# M617E.net
KiCad netlist of a schematic drawn in EAGLE
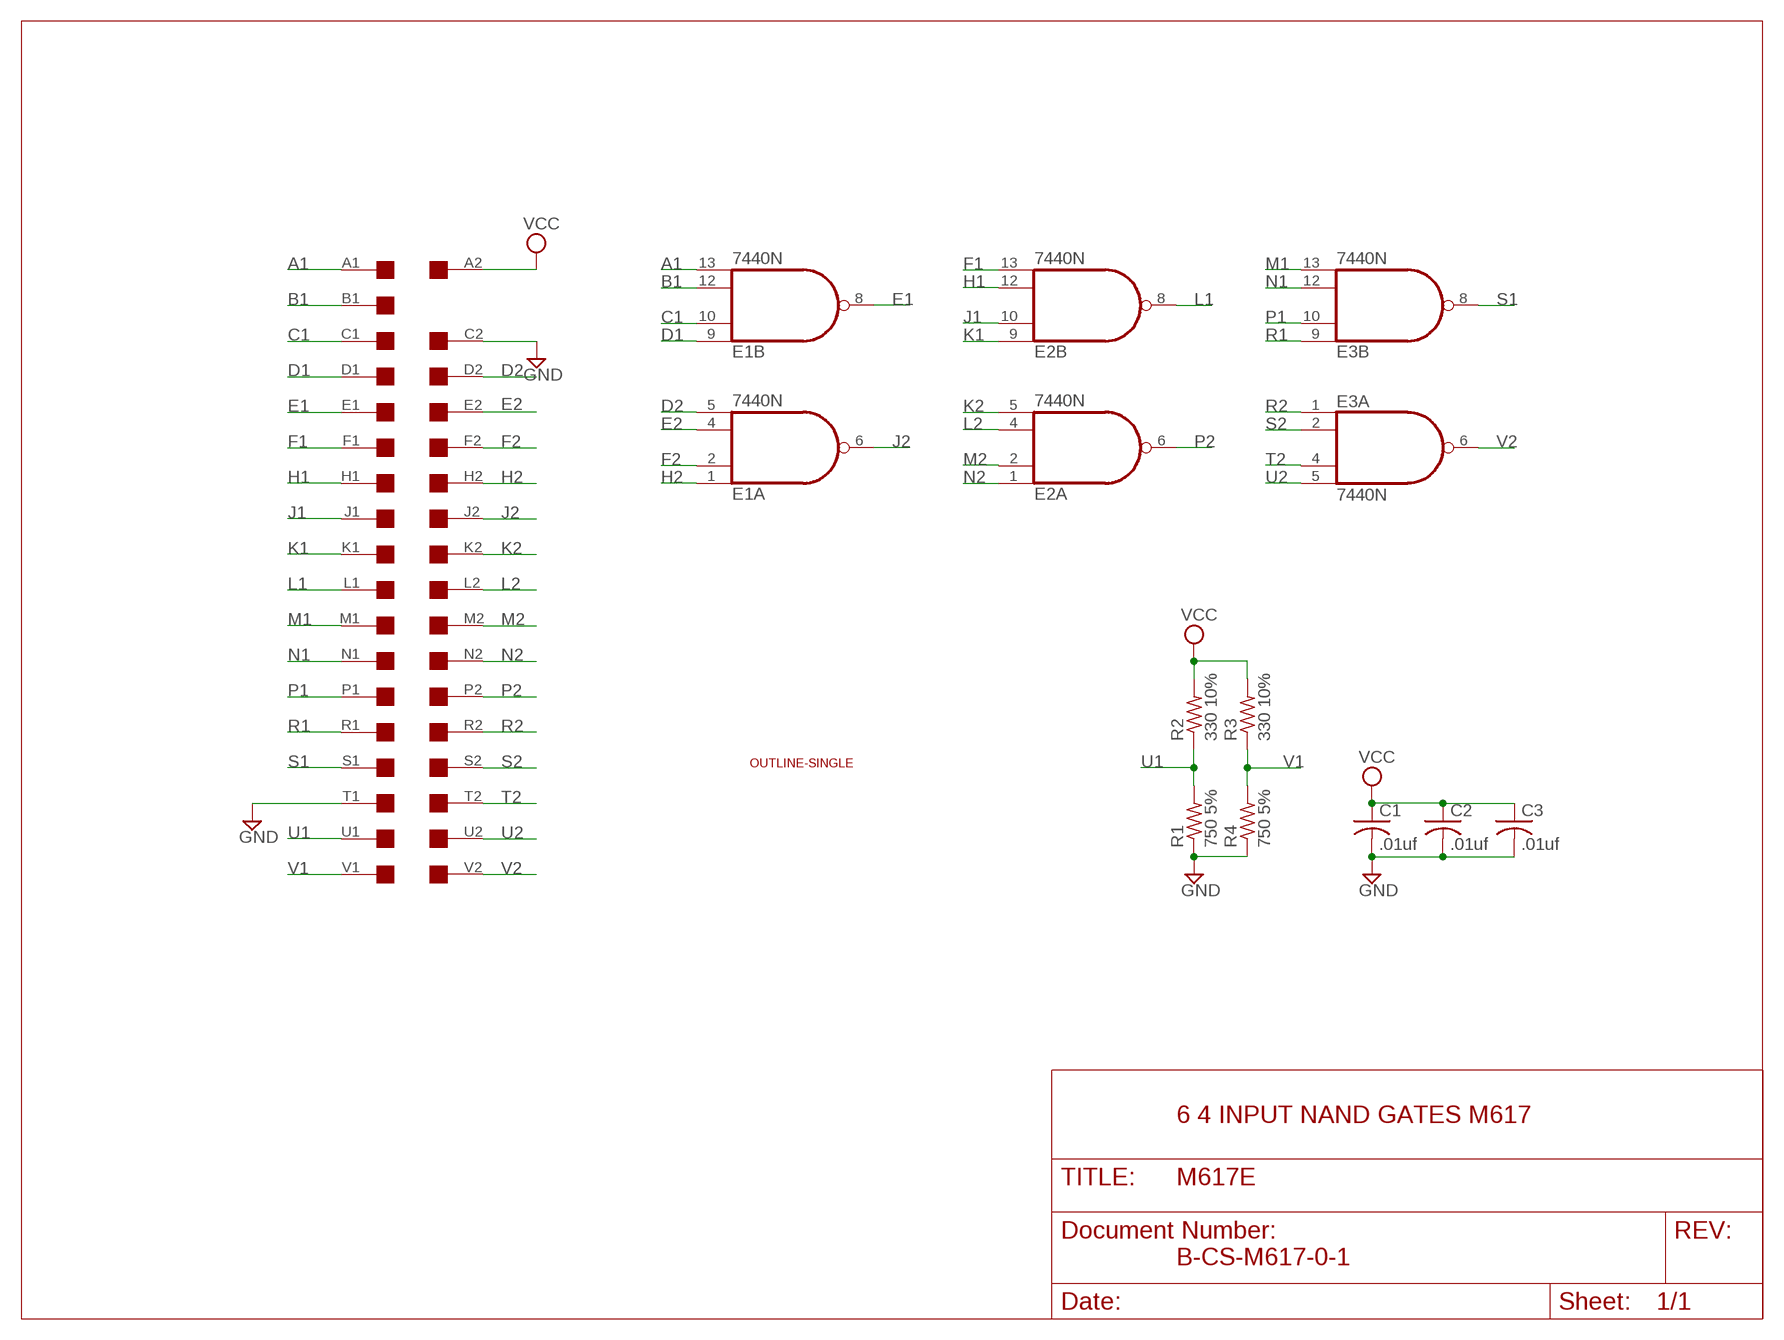
[diagram p0: schematic, sheet 1]

(export (version "E")
  (design (tool "Eeschema 10.0.6"))
  (components
    (comp (ref "C1")
      (value ".01uf")
      (footprint "eagle-import:C050-025X075")
      (libsource (lib "eagle-import") (part "C-US050-025X075"))
    )
    (comp (ref "C2")
      (value ".01uf")
      (footprint "eagle-import:C050-025X075")
      (libsource (lib "eagle-import") (part "C-US050-025X075"))
    )
    (comp (ref "C3")
      (value ".01uf")
      (footprint "eagle-import:C050-025X075")
      (libsource (lib "eagle-import") (part "C-US050-025X075"))
    )
    (comp (ref "E1")
      (value "7440N")
      (footprint "eagle-import:DIL14")
      (libsource (lib "eagle-import") (part "7420NS"))
    )
    (comp (ref "E2")
      (value "7440N")
      (footprint "eagle-import:DIL14")
      (libsource (lib "eagle-import") (part "7420NS"))
    )
    (comp (ref "E3")
      (value "7440N")
      (footprint "eagle-import:DIL14")
      (libsource (lib "eagle-import") (part "7420NS"))
    )
    (comp (ref "R1")
      (value "750 5%")
      (footprint "eagle-import:0207_10")
      (libsource (lib "eagle-import") (part "R-US_0207/10"))
    )
    (comp (ref "R2")
      (value "330 10%")
      (footprint "eagle-import:0207_10")
      (libsource (lib "eagle-import") (part "R-US_0207/10"))
    )
    (comp (ref "R3")
      (value "330 10%")
      (footprint "eagle-import:0207_10")
      (libsource (lib "eagle-import") (part "R-US_0207/10"))
    )
    (comp (ref "R4")
      (value "750 5%")
      (footprint "eagle-import:0207_10")
      (libsource (lib "eagle-import") (part "R-US_0207/10"))
    )
    (comp (ref "U$1")
      (value "SINGLE")
      (footprint "eagle-import:EDGE-CON2")
      (libsource (lib "eagle-import") (part "SINGLE"))
    )
    (comp (ref "U$4")
      (value "OUTLINE-SINGLE")
      (footprint "eagle-import:SINGLE")
      (libsource (lib "eagle-import") (part "OUTLINE-SINGLE"))
    )
  )
  (nets
    (net (code "1") (name "/A1") (class "Default")
      (node (ref "E1") (pin "13") (pinfunction "I3_13") (pintype "input"))
      (node (ref "U$1") (pin "A1") (pinfunction "1_A1") (pintype "bidirectional"))
    )
    (net (code "2") (name "/B1") (class "Default")
      (node (ref "E1") (pin "12") (pinfunction "I2_12") (pintype "input"))
      (node (ref "U$1") (pin "B1") (pinfunction "1_B1") (pintype "bidirectional"))
    )
    (net (code "3") (name "/C1") (class "Default")
      (node (ref "E1") (pin "10") (pinfunction "I1_10") (pintype "input"))
      (node (ref "U$1") (pin "C1") (pinfunction "1_C1") (pintype "bidirectional"))
    )
    (net (code "4") (name "/D1") (class "Default")
      (node (ref "E1") (pin "9") (pinfunction "I0_9") (pintype "input"))
      (node (ref "U$1") (pin "D1") (pinfunction "1_D1") (pintype "bidirectional"))
    )
    (net (code "5") (name "/D2") (class "Default")
      (node (ref "E1") (pin "5") (pinfunction "I3_5") (pintype "input"))
      (node (ref "U$1") (pin "D2") (pinfunction "1_D2") (pintype "bidirectional"))
    )
    (net (code "6") (name "/E1") (class "Default")
      (node (ref "E1") (pin "8") (pinfunction "O_8") (pintype "output"))
      (node (ref "U$1") (pin "E1") (pinfunction "1_E1") (pintype "bidirectional"))
    )
    (net (code "7") (name "/E2") (class "Default")
      (node (ref "E1") (pin "4") (pinfunction "I2_4") (pintype "input"))
      (node (ref "U$1") (pin "E2") (pinfunction "1_E2") (pintype "bidirectional"))
    )
    (net (code "8") (name "/F1") (class "Default")
      (node (ref "E2") (pin "13") (pinfunction "I3_13") (pintype "input"))
      (node (ref "U$1") (pin "F1") (pinfunction "1_F1") (pintype "bidirectional"))
    )
    (net (code "9") (name "/F2") (class "Default")
      (node (ref "E1") (pin "2") (pinfunction "I1_2") (pintype "input"))
      (node (ref "U$1") (pin "F2") (pinfunction "1_F2") (pintype "bidirectional"))
    )
    (net (code "10") (name "/H1") (class "Default")
      (node (ref "E2") (pin "12") (pinfunction "I2_12") (pintype "input"))
      (node (ref "U$1") (pin "H1") (pinfunction "1_H1") (pintype "bidirectional"))
    )
    (net (code "11") (name "/H2") (class "Default")
      (node (ref "E1") (pin "1") (pinfunction "I0_1") (pintype "input"))
      (node (ref "U$1") (pin "H2") (pinfunction "1_H2") (pintype "bidirectional"))
    )
    (net (code "12") (name "/J1") (class "Default")
      (node (ref "E2") (pin "10") (pinfunction "I1_10") (pintype "input"))
      (node (ref "U$1") (pin "J1") (pinfunction "1_J1") (pintype "bidirectional"))
    )
    (net (code "13") (name "/J2") (class "Default")
      (node (ref "E1") (pin "6") (pinfunction "O_6") (pintype "output"))
      (node (ref "U$1") (pin "J2") (pinfunction "1_J2") (pintype "bidirectional"))
    )
    (net (code "14") (name "/K1") (class "Default")
      (node (ref "E2") (pin "9") (pinfunction "I0_9") (pintype "input"))
      (node (ref "U$1") (pin "K1") (pinfunction "1_K1") (pintype "bidirectional"))
    )
    (net (code "15") (name "/K2") (class "Default")
      (node (ref "E2") (pin "5") (pinfunction "I3_5") (pintype "input"))
      (node (ref "U$1") (pin "K2") (pinfunction "1_K2") (pintype "bidirectional"))
    )
    (net (code "16") (name "/L1") (class "Default")
      (node (ref "E2") (pin "8") (pinfunction "O_8") (pintype "output"))
      (node (ref "U$1") (pin "L1") (pinfunction "1_L1") (pintype "bidirectional"))
    )
    (net (code "17") (name "/L2") (class "Default")
      (node (ref "E2") (pin "4") (pinfunction "I2_4") (pintype "input"))
      (node (ref "U$1") (pin "L2") (pinfunction "1_L2") (pintype "bidirectional"))
    )
    (net (code "18") (name "/M1") (class "Default")
      (node (ref "E3") (pin "13") (pinfunction "I3_13") (pintype "input"))
      (node (ref "U$1") (pin "M1") (pinfunction "1_M1") (pintype "bidirectional"))
    )
    (net (code "19") (name "/M2") (class "Default")
      (node (ref "E2") (pin "2") (pinfunction "I1_2") (pintype "input"))
      (node (ref "U$1") (pin "M2") (pinfunction "1_M2") (pintype "bidirectional"))
    )
    (net (code "20") (name "/N1") (class "Default")
      (node (ref "E3") (pin "12") (pinfunction "I2_12") (pintype "input"))
      (node (ref "U$1") (pin "N1") (pinfunction "1_N1") (pintype "bidirectional"))
    )
    (net (code "21") (name "/N2") (class "Default")
      (node (ref "E2") (pin "1") (pinfunction "I0_1") (pintype "input"))
      (node (ref "U$1") (pin "N2") (pinfunction "1_N2") (pintype "bidirectional"))
    )
    (net (code "22") (name "/P1") (class "Default")
      (node (ref "E3") (pin "10") (pinfunction "I1_10") (pintype "input"))
      (node (ref "U$1") (pin "P1") (pinfunction "1_P1") (pintype "bidirectional"))
    )
    (net (code "23") (name "/P2") (class "Default")
      (node (ref "E2") (pin "6") (pinfunction "O_6") (pintype "output"))
      (node (ref "U$1") (pin "P2") (pinfunction "1_P2") (pintype "bidirectional"))
    )
    (net (code "24") (name "/R1") (class "Default")
      (node (ref "E3") (pin "9") (pinfunction "I0_9") (pintype "input"))
      (node (ref "U$1") (pin "R1") (pinfunction "1_R1") (pintype "bidirectional"))
    )
    (net (code "25") (name "/R2") (class "Default")
      (node (ref "E3") (pin "1") (pinfunction "I0_1") (pintype "input"))
      (node (ref "U$1") (pin "R2") (pinfunction "1_R2") (pintype "bidirectional"))
    )
    (net (code "26") (name "/S1") (class "Default")
      (node (ref "E3") (pin "8") (pinfunction "O_8") (pintype "output"))
      (node (ref "U$1") (pin "S1") (pinfunction "1_S1") (pintype "bidirectional"))
    )
    (net (code "27") (name "/S2") (class "Default")
      (node (ref "E3") (pin "2") (pinfunction "I1_2") (pintype "input"))
      (node (ref "U$1") (pin "S2") (pinfunction "1_S2") (pintype "bidirectional"))
    )
    (net (code "28") (name "/T2") (class "Default")
      (node (ref "E3") (pin "4") (pinfunction "I2_4") (pintype "input"))
      (node (ref "U$1") (pin "T2") (pinfunction "1_T2") (pintype "bidirectional"))
    )
    (net (code "29") (name "/U1") (class "Default")
      (node (ref "R1") (pin "2") (pinfunction "2_2") (pintype "passive"))
      (node (ref "R2") (pin "1") (pinfunction "1_1") (pintype "passive"))
      (node (ref "U$1") (pin "U1") (pinfunction "1_U1") (pintype "bidirectional"))
    )
    (net (code "30") (name "/U2") (class "Default")
      (node (ref "E3") (pin "5") (pinfunction "I3_5") (pintype "input"))
      (node (ref "U$1") (pin "U2") (pinfunction "1_U2") (pintype "bidirectional"))
    )
    (net (code "31") (name "/V1") (class "Default")
      (node (ref "R3") (pin "1") (pinfunction "1_1") (pintype "passive"))
      (node (ref "R4") (pin "2") (pinfunction "2_2") (pintype "passive"))
      (node (ref "U$1") (pin "V1") (pinfunction "1_V1") (pintype "bidirectional"))
    )
    (net (code "32") (name "/V2") (class "Default")
      (node (ref "E3") (pin "6") (pinfunction "O_6") (pintype "output"))
      (node (ref "U$1") (pin "V2") (pinfunction "1_V2") (pintype "bidirectional"))
    )
    (net (code "33") (name "GND") (class "Default")
      (node (ref "C1") (pin "2") (pinfunction "2_2") (pintype "passive"))
      (node (ref "C2") (pin "2") (pinfunction "2_2") (pintype "passive"))
      (node (ref "C3") (pin "2") (pinfunction "2_2") (pintype "passive"))
      (node (ref "R1") (pin "1") (pinfunction "1_1") (pintype "passive"))
      (node (ref "R4") (pin "1") (pinfunction "1_1") (pintype "passive"))
      (node (ref "U$1") (pin "C2") (pinfunction "1_C2") (pintype "bidirectional"))
      (node (ref "U$1") (pin "T1") (pinfunction "1_T1") (pintype "bidirectional"))
    )
    (net (code "34") (name "VCC") (class "Default")
      (node (ref "C1") (pin "1") (pinfunction "1_1") (pintype "passive"))
      (node (ref "C2") (pin "1") (pinfunction "1_1") (pintype "passive"))
      (node (ref "C3") (pin "1") (pinfunction "1_1") (pintype "passive"))
      (node (ref "R2") (pin "2") (pinfunction "2_2") (pintype "passive"))
      (node (ref "R3") (pin "2") (pinfunction "2_2") (pintype "passive"))
      (node (ref "U$1") (pin "A2") (pinfunction "1_A2") (pintype "bidirectional"))
    )
  )
)
